# Synapse_all.net
KiCad netlist of a schematic drawn in Altium Designer
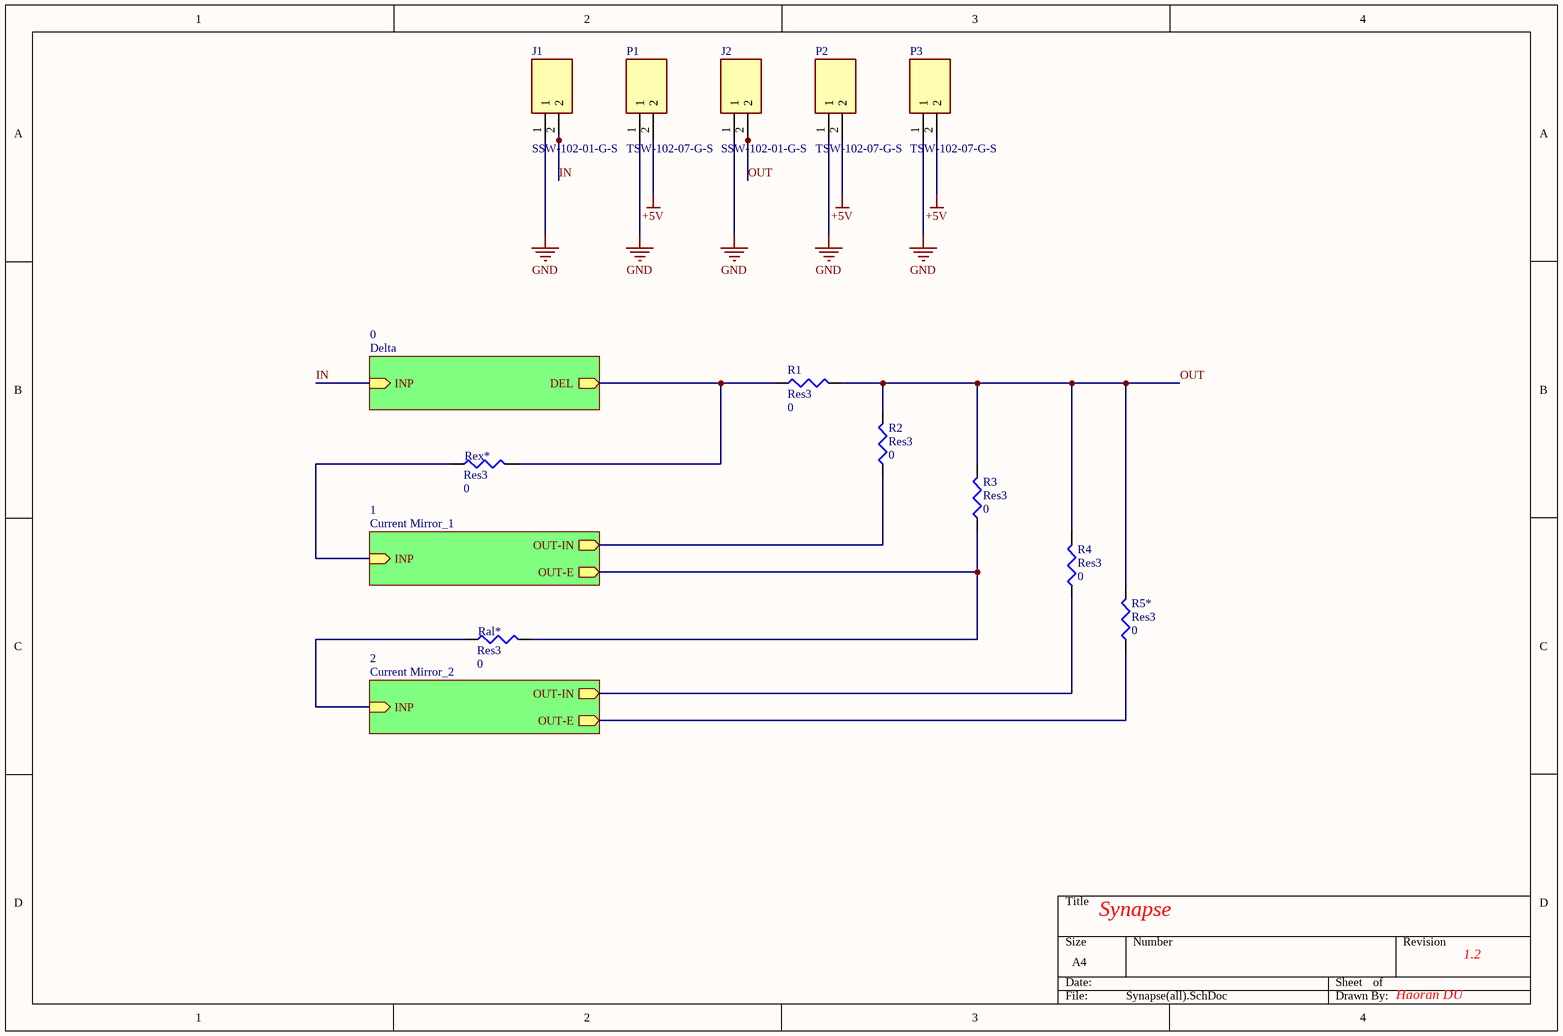
[diagram p0: Synapse(all).SchDoc]

(export (version "E")
  (design (tool "Eeschema 10.0.6"))
  (components
    (comp (ref "J1")
      (value "SSW-102-01-G-S")
      (footprint "SSW-102-XX-YYY-S")
      (description "Connector")
      (fields (field (name "MOUSER PART NUMBER") "200-SSW10201GS"))
      (libsource (lib "*") (part "SSW-102-01-G-S"))
    )
    (comp (ref "J2")
      (value "SSW-102-01-G-S")
      (footprint "SSW-102-XX-YYY-S")
      (description "Connector")
      (fields (field (name "MOUSER PART NUMBER") "200-SSW10201GS"))
      (libsource (lib "*") (part "SSW-102-01-G-S"))
    )
    (comp (ref "P1")
      (value "TSW-102-07-G-S")
      (footprint "TSW-102-XX-YY-S")
      (description "Connector")
      (fields (field (name "MOUSER PART NUMBER") "200-TSW10207GS"))
      (libsource (lib "*") (part "TSW-102-07-G-S"))
    )
    (comp (ref "P2")
      (value "TSW-102-07-G-S")
      (footprint "TSW-102-XX-YY-S")
      (description "Connector")
      (fields (field (name "MOUSER PART NUMBER") "200-TSW10207GS"))
      (libsource (lib "*") (part "TSW-102-07-G-S"))
    )
    (comp (ref "P3")
      (value "TSW-102-07-G-S")
      (footprint "TSW-102-XX-YY-S")
      (description "Connector")
      (fields (field (name "MOUSER PART NUMBER") "200-TSW10207GS"))
      (libsource (lib "*") (part "TSW-102-07-G-S"))
    )
    (comp (ref "R1")
      (value "Res3")
      (footprint "J1-0603")
      (description "Resistor")
      (fields (field (name "ALTIUM_VALUE") "0") (field (name "PUBLISHER") "Altium Limited"))
      (libsource (lib "Miscellaneous Devices") (part "Res3"))
    )
    (comp (ref "R2")
      (value "Res3")
      (footprint "J1-0603")
      (description "Resistor")
      (fields (field (name "ALTIUM_VALUE") "0") (field (name "PUBLISHER") "Altium Limited"))
      (libsource (lib "Miscellaneous Devices") (part "Res3"))
    )
    (comp (ref "R3")
      (value "Res3")
      (footprint "J1-0603")
      (description "Resistor")
      (fields (field (name "ALTIUM_VALUE") "0") (field (name "PUBLISHER") "Altium Limited"))
      (libsource (lib "Miscellaneous Devices") (part "Res3"))
    )
    (comp (ref "R4")
      (value "Res3")
      (footprint "J1-0603")
      (description "Resistor")
      (fields (field (name "ALTIUM_VALUE") "0") (field (name "PUBLISHER") "Altium Limited"))
      (libsource (lib "Miscellaneous Devices") (part "Res3"))
    )
    (comp (ref "R5*")
      (value "Res3")
      (footprint "J1-0603")
      (description "Resistor")
      (fields (field (name "ALTIUM_VALUE") "0") (field (name "PUBLISHER") "Altium Limited"))
      (libsource (lib "Miscellaneous Devices") (part "Res3"))
    )
    (comp (ref "Ral*")
      (value "Res3")
      (footprint "J1-0603")
      (description "Resistor")
      (fields (field (name "ALTIUM_VALUE") "0") (field (name "PUBLISHER") "Altium Limited"))
      (libsource (lib "Miscellaneous Devices") (part "Res3"))
    )
    (comp (ref "Rex*")
      (value "Res3")
      (footprint "J1-0603")
      (description "Resistor")
      (fields (field (name "ALTIUM_VALUE") "0") (field (name "PUBLISHER") "Altium Limited"))
      (libsource (lib "Miscellaneous Devices") (part "Res3"))
    )
  )
  (nets
    (net (code "1") (name "+5V") (class "Default")
      (node (ref "P1") (pin "2") (pinfunction "2_2") (pintype "passive"))
      (node (ref "P2") (pin "2") (pinfunction "2_2") (pintype "passive"))
      (node (ref "P3") (pin "2") (pinfunction "2_2") (pintype "passive"))
    )
    (net (code "2") (name "/DEL") (class "Default")
      (node (ref "R1") (pin "1") (pinfunction "1_1") (pintype "passive"))
      (node (ref "Rex*") (pin "2") (pinfunction "2_2") (pintype "passive"))
    )
    (net (code "3") (name "/IN") (class "Default")
      (node (ref "J1") (pin "2") (pinfunction "2_2") (pintype "passive"))
    )
    (net (code "4") (name "/INP") (class "Default")
      (node (ref "Rex*") (pin "1") (pinfunction "1_1") (pintype "passive"))
    )
    (net (code "5") (name "/INP_1") (class "Default")
      (node (ref "Ral*") (pin "1") (pinfunction "1_1") (pintype "passive"))
    )
    (net (code "6") (name "/OUT") (class "Default")
      (node (ref "J2") (pin "2") (pinfunction "2_2") (pintype "passive"))
      (node (ref "R1") (pin "2") (pinfunction "2_2") (pintype "passive"))
      (node (ref "R2") (pin "2") (pinfunction "2_2") (pintype "passive"))
      (node (ref "R3") (pin "2") (pinfunction "2_2") (pintype "passive"))
      (node (ref "R4") (pin "2") (pinfunction "2_2") (pintype "passive"))
      (node (ref "R5*") (pin "2") (pinfunction "2_2") (pintype "passive"))
    )
    (net (code "7") (name "/OUT-E") (class "Default")
      (node (ref "R5*") (pin "1") (pinfunction "1_1") (pintype "passive"))
    )
    (net (code "8") (name "/OUT-E_1") (class "Default")
      (node (ref "R3") (pin "1") (pinfunction "1_1") (pintype "passive"))
      (node (ref "Ral*") (pin "2") (pinfunction "2_2") (pintype "passive"))
    )
    (net (code "9") (name "/OUT-IN") (class "Default")
      (node (ref "R4") (pin "1") (pinfunction "1_1") (pintype "passive"))
    )
    (net (code "10") (name "/OUT-IN_1") (class "Default")
      (node (ref "R2") (pin "1") (pinfunction "1_1") (pintype "passive"))
    )
    (net (code "11") (name "GND") (class "Default")
      (node (ref "J1") (pin "1") (pinfunction "1_1") (pintype "passive"))
      (node (ref "J2") (pin "1") (pinfunction "1_1") (pintype "passive"))
      (node (ref "P1") (pin "1") (pinfunction "1_1") (pintype "passive"))
      (node (ref "P2") (pin "1") (pinfunction "1_1") (pintype "passive"))
      (node (ref "P3") (pin "1") (pinfunction "1_1") (pintype "passive"))
    )
  )
)
